# Reefing-PSU.net
KiCad netlist of a schematic drawn in Altium Designer
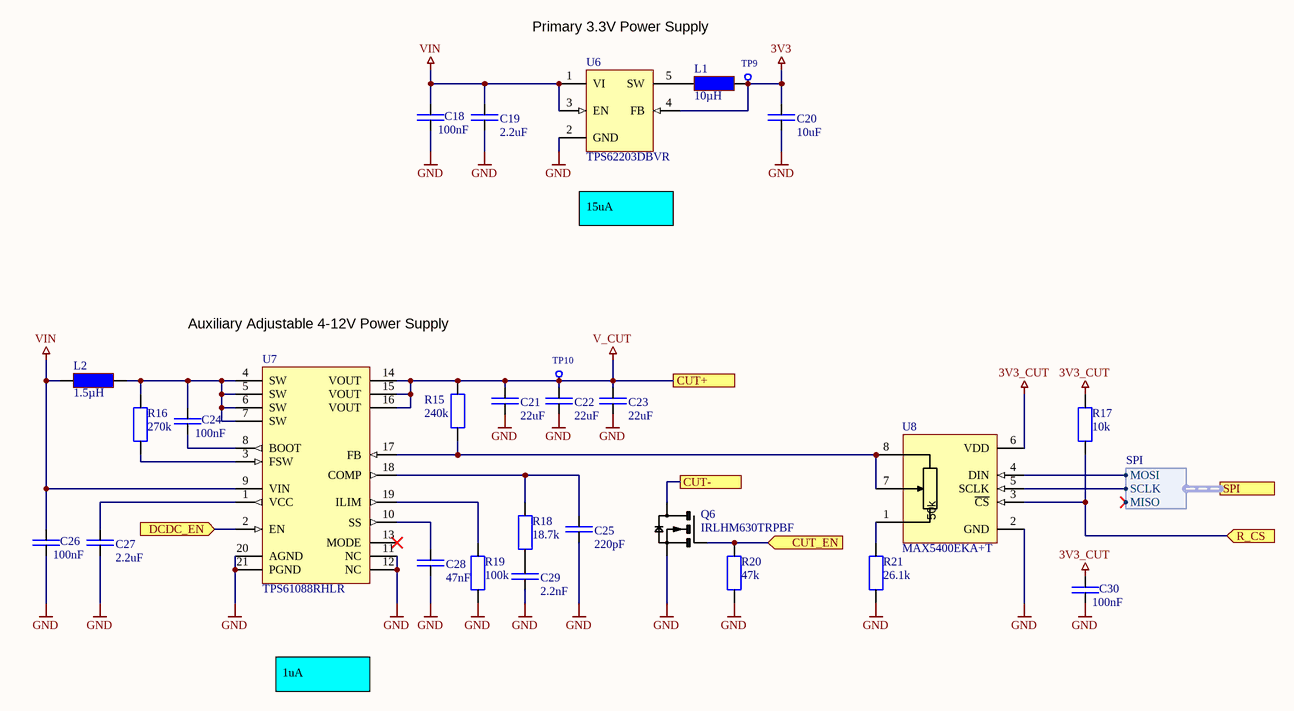
[diagram p0: Reefing-PSU.SchDoc]

(export (version "E")
  (design (tool "Eeschema 10.0.6"))
  (components
    (comp (ref "C18")
      (value "100nF")
      (footprint "SMD Keramikkondensator 0805")
      (description "SMD Ceramic Capacitor E6")
      (libsource (lib "Ceramic Capacitors-E6") (part "E6 - 100nF"))
    )
    (comp (ref "C19")
      (value "2.2uF")
      (footprint "SMD Keramikkondensator 0805")
      (description "SMD Ceramic Capacitor E6")
      (libsource (lib "Ceramic Capacitors-E6") (part "E6 - 2.2uF"))
    )
    (comp (ref "C20")
      (value "10uF")
      (footprint "SMD Keramikkondensator 0805")
      (description "SMD Ceramic Capacitor E6")
      (libsource (lib "Ceramic Capacitors-E6") (part "E6 - 10uF"))
    )
    (comp (ref "C21")
      (value "22uF")
      (footprint "SMD Keramikkondensator 0805")
      (description "SMD Ceramic Capacitor E6")
      (libsource (lib "Ceramic Capacitors-E6") (part "E6 - 22uF"))
    )
    (comp (ref "C22")
      (value "22uF")
      (footprint "SMD Keramikkondensator 0805")
      (description "SMD Ceramic Capacitor E6")
      (libsource (lib "Ceramic Capacitors-E6") (part "E6 - 22uF"))
    )
    (comp (ref "C23")
      (value "22uF")
      (footprint "SMD Keramikkondensator 0805")
      (description "SMD Ceramic Capacitor E6")
      (libsource (lib "Ceramic Capacitors-E6") (part "E6 - 22uF"))
    )
    (comp (ref "C24")
      (value "100nF")
      (footprint "SMD Keramikkondensator 0805")
      (description "SMD Ceramic Capacitor E6")
      (libsource (lib "Ceramic Capacitors-E6") (part "E6 - 100nF"))
    )
    (comp (ref "C25")
      (value "220pF")
      (footprint "SMD Keramikkondensator 0805")
      (description "SMD Ceramic Capacitor E6")
      (libsource (lib "Ceramic Capacitors-E6") (part "E6 - 220pF"))
    )
    (comp (ref "C26")
      (value "100nF")
      (footprint "SMD Keramikkondensator 0805")
      (description "SMD Ceramic Capacitor E6")
      (libsource (lib "Ceramic Capacitors-E6") (part "E6 - 100nF"))
    )
    (comp (ref "C27")
      (value "2.2uF")
      (footprint "SMD Keramikkondensator 0805")
      (description "SMD Ceramic Capacitor E6")
      (libsource (lib "Ceramic Capacitors-E6") (part "E6 - 2.2uF"))
    )
    (comp (ref "C28")
      (value "47nF")
      (footprint "SMD Keramikkondensator 0805")
      (description "SMD Ceramic Capacitor E6")
      (libsource (lib "Ceramic Capacitors-E6") (part "E6 - 47nF"))
    )
    (comp (ref "C29")
      (value "2.2nF")
      (footprint "SMD Keramikkondensator 0805")
      (description "SMD Ceramic Capacitor E6")
      (libsource (lib "Ceramic Capacitors-E6") (part "E6 - 2.2nF"))
    )
    (comp (ref "C30")
      (value "100nF")
      (footprint "SMD Keramikkondensator 0805")
      (description "SMD Ceramic Capacitor E6")
      (libsource (lib "Ceramic Capacitors-E6") (part "E6 - 100nF"))
    )
    (comp (ref "L1")
      (value "10µH")
      (footprint "SMD Inductor 4x4x1.8")
      (description "165mOhm SMD, 1.6A")
      (libsource (lib "Inductors") (part "Inductor 10µH / 1.6A"))
    )
    (comp (ref "L2")
      (value "1.5µH")
      (footprint "SMD Inductor 7.1x6.6")
      (description "8.5mΩ SMD, 7.1x6.6x5mm")
      (libsource (lib "Inductors") (part "Inductor 1.5µH / 10A"))
    )
    (comp (ref "Q6")
      (value "IRLHM630TRPBF")
      (footprint "SMD MOSFET DFN 3x3 EP")
      (description "N-Channel 30V 21A 3.5mOhm@4.5V")
      (libsource (lib "Electronic Switches") (part "IRLHM630TRPBF"))
    )
    (comp (ref "R15")
      (value "240k")
      (footprint "SMD Widerstand 0805")
      (description "SMD Chip Resistor E24")
      (libsource (lib "Resistors-E24") (part "E24 - 240k"))
    )
    (comp (ref "R16")
      (value "270k")
      (footprint "SMD Widerstand 0805")
      (description "SMD Chip Resistor E24")
      (libsource (lib "Resistors-E24") (part "E24 - 270k"))
    )
    (comp (ref "R17")
      (value "10k")
      (footprint "SMD Widerstand 0805")
      (description "SMD Chip Resistor E24")
      (libsource (lib "Resistors-E24") (part "E24 - 10k"))
    )
    (comp (ref "R18")
      (value "18.7k")
      (footprint "SMD Widerstand 0805")
      (description "SMD Chip Resistor E96")
      (libsource (lib "Resistors-E96") (part "E96 - 18.7k"))
    )
    (comp (ref "R19")
      (value "100k")
      (footprint "SMD Widerstand 0805")
      (description "SMD Chip Resistor E24")
      (libsource (lib "Resistors-E24") (part "E24 - 100k"))
    )
    (comp (ref "R20")
      (value "47k")
      (footprint "SMD Widerstand 0805")
      (description "SMD Chip Resistor E24")
      (libsource (lib "Resistors-E24") (part "E24 - 47k"))
    )
    (comp (ref "R21")
      (value "26.1k")
      (footprint "SMD Widerstand 0805")
      (description "SMD Chip Resistor E96")
      (libsource (lib "Resistors-E96") (part "E96 - 26.1k"))
    )
    (comp (ref "TP9")
      (value "X-TP")
      (footprint "SMD Testpunkt Ø1mm")
      (description "Testpunkt")
      (libsource (lib "Fleet-Monitor") (part "X-TP"))
    )
    (comp (ref "TP10")
      (value "X-TP")
      (footprint "SMD Testpunkt Ø1mm")
      (description "Testpunkt")
      (libsource (lib "Fleet-Monitor") (part "X-TP"))
    )
    (comp (ref "U6")
      (value "TPS62203DBVR")
      (footprint "SMD IC SOT-23-5")
      (libsource (lib "Voltage-Converter") (part "TPS62203DBVR"))
    )
    (comp (ref "U7")
      (value "TPS61088RHLR")
      (footprint "SMD IC VQFN-20")
      (description "10-A Fully-Integrated Synchronous Boost Converter")
      (libsource (lib "Voltage-Converter") (part "TPS61088RHLR"))
    )
    (comp (ref "U8")
      (value "MAX5400EKA+T")
      (footprint "SMD IC SOT-23-8")
      (description "Low-Drift Digital Potentiometer")
      (libsource (lib "Analog") (part "MAX5400EKA+T"))
    )
  )
  (nets
    (net (code "2") (name "/CUT-") (class "Default")
      (node (ref "Q6") (pin "D") (pinfunction "D_D") (pintype "passive"))
    )
    (net (code "3") (name "/CUT_EN") (class "Default")
      (node (ref "Q6") (pin "G") (pinfunction "G_G") (pintype "passive"))
      (node (ref "R20") (pin "2") (pinfunction "2_2") (pintype "passive"))
    )
    (net (code "4") (name "/DCDC_EN") (class "Default")
      (node (ref "U7") (pin "2") (pinfunction "EN_2") (pintype "input"))
    )
    (net (code "5") (name "/MOSI") (class "Default")
      (node (ref "U8") (pin "4") (pinfunction "DIN_4") (pintype "input"))
    )
    (net (code "6") (name "/R_CS") (class "Default")
      (node (ref "R17") (pin "1") (pinfunction "1_1") (pintype "passive"))
      (node (ref "U8") (pin "3") (pinfunction "~{CS}_3") (pintype "input"))
    )
    (net (code "7") (name "/SCLK") (class "Default")
      (node (ref "U8") (pin "5") (pinfunction "SCLK_5") (pintype "input"))
    )
    (net (code "9") (name "3V3") (class "Default")
      (node (ref "C20") (pin "2") (pinfunction "2_2") (pintype "passive"))
      (node (ref "L1") (pin "2") (pinfunction "2_2") (pintype "passive"))
      (node (ref "TP9") (pin "1") (pinfunction "1_1") (pintype "passive"))
      (node (ref "U6") (pin "4") (pinfunction "FB_4") (pintype "input"))
    )
    (net (code "10") (name "3V3_CUT") (class "Default")
      (node (ref "C30") (pin "2") (pinfunction "2_2") (pintype "passive"))
      (node (ref "R17") (pin "2") (pinfunction "2_2") (pintype "passive"))
      (node (ref "U8") (pin "6") (pinfunction "VDD_6") (pintype "passive"))
    )
    (net (code "11") (name "GND") (class "Default")
      (node (ref "C18") (pin "1") (pinfunction "1_1") (pintype "passive"))
      (node (ref "C19") (pin "1") (pinfunction "1_1") (pintype "passive"))
      (node (ref "C20") (pin "1") (pinfunction "1_1") (pintype "passive"))
      (node (ref "C21") (pin "1") (pinfunction "1_1") (pintype "passive"))
      (node (ref "C22") (pin "1") (pinfunction "1_1") (pintype "passive"))
      (node (ref "C23") (pin "1") (pinfunction "1_1") (pintype "passive"))
      (node (ref "C25") (pin "1") (pinfunction "1_1") (pintype "passive"))
      (node (ref "C26") (pin "1") (pinfunction "1_1") (pintype "passive"))
      (node (ref "C27") (pin "1") (pinfunction "1_1") (pintype "passive"))
      (node (ref "C28") (pin "1") (pinfunction "1_1") (pintype "passive"))
      (node (ref "C29") (pin "1") (pinfunction "1_1") (pintype "passive"))
      (node (ref "C30") (pin "1") (pinfunction "1_1") (pintype "passive"))
      (node (ref "Q6") (pin "S") (pinfunction "S_S") (pintype "passive"))
      (node (ref "R19") (pin "1") (pinfunction "1_1") (pintype "passive"))
      (node (ref "R20") (pin "1") (pinfunction "1_1") (pintype "passive"))
      (node (ref "R21") (pin "1") (pinfunction "1_1") (pintype "passive"))
      (node (ref "U6") (pin "2") (pinfunction "GND_2") (pintype "passive"))
      (node (ref "U7") (pin "11") (pinfunction "NC_11") (pintype "passive"))
      (node (ref "U7") (pin "12") (pinfunction "NC_12") (pintype "passive"))
      (node (ref "U7") (pin "20") (pinfunction "AGND_20") (pintype "passive"))
      (node (ref "U7") (pin "21") (pinfunction "PGND_21") (pintype "passive"))
      (node (ref "U8") (pin "2") (pinfunction "GND_2") (pintype "passive"))
    )
    (net (code "12") (name "Net-(C24-Pad2)") (class "Default")
      (node (ref "C24") (pin "2") (pinfunction "2_2") (pintype "passive"))
      (node (ref "L2") (pin "2") (pinfunction "2_2") (pintype "passive"))
      (node (ref "R16") (pin "2") (pinfunction "2_2") (pintype "passive"))
      (node (ref "U7") (pin "4") (pinfunction "SW_4") (pintype "passive"))
      (node (ref "U7") (pin "5") (pinfunction "SW_5") (pintype "passive"))
      (node (ref "U7") (pin "6") (pinfunction "SW_6") (pintype "passive"))
      (node (ref "U7") (pin "7") (pinfunction "SW_7") (pintype "passive"))
    )
    (net (code "13") (name "Net-(C29-Pad2)") (class "Default")
      (node (ref "C29") (pin "2") (pinfunction "2_2") (pintype "passive"))
      (node (ref "R18") (pin "1") (pinfunction "1_1") (pintype "passive"))
    )
    (net (code "14") (name "Net-(U6-SW)") (class "Default")
      (node (ref "L1") (pin "1") (pinfunction "1_1") (pintype "passive"))
      (node (ref "U6") (pin "5") (pinfunction "SW_5") (pintype "passive"))
    )
    (net (code "15") (name "Net-(U7-BOOT)") (class "Default")
      (node (ref "C24") (pin "1") (pinfunction "1_1") (pintype "passive"))
      (node (ref "U7") (pin "8") (pinfunction "BOOT_8") (pintype "output"))
    )
    (net (code "16") (name "Net-(U7-COMP)") (class "Default")
      (node (ref "C25") (pin "2") (pinfunction "2_2") (pintype "passive"))
      (node (ref "R18") (pin "2") (pinfunction "2_2") (pintype "passive"))
      (node (ref "U7") (pin "18") (pinfunction "COMP_18") (pintype "output"))
    )
    (net (code "17") (name "Net-(U7-FB)") (class "Default")
      (node (ref "R15") (pin "1") (pinfunction "1_1") (pintype "passive"))
      (node (ref "U7") (pin "17") (pinfunction "FB_17") (pintype "input"))
      (node (ref "U8") (pin "7") (pinfunction "W_7") (pintype "passive"))
      (node (ref "U8") (pin "8") (pinfunction "H_8") (pintype "passive"))
    )
    (net (code "18") (name "Net-(U7-FSW)") (class "Default")
      (node (ref "R16") (pin "1") (pinfunction "1_1") (pintype "passive"))
      (node (ref "U7") (pin "3") (pinfunction "FSW_3") (pintype "input"))
    )
    (net (code "19") (name "Net-(U7-ILIM)") (class "Default")
      (node (ref "R19") (pin "2") (pinfunction "2_2") (pintype "passive"))
      (node (ref "U7") (pin "19") (pinfunction "ILIM_19") (pintype "output"))
    )
    (net (code "20") (name "Net-(U7-SS)") (class "Default")
      (node (ref "C28") (pin "2") (pinfunction "2_2") (pintype "passive"))
      (node (ref "U7") (pin "10") (pinfunction "SS_10") (pintype "output"))
    )
    (net (code "21") (name "Net-(U7-VCC)") (class "Default")
      (node (ref "C27") (pin "2") (pinfunction "2_2") (pintype "passive"))
      (node (ref "U7") (pin "1") (pinfunction "VCC_1") (pintype "output"))
    )
    (net (code "22") (name "Net-(U8-L)") (class "Default")
      (node (ref "R21") (pin "2") (pinfunction "2_2") (pintype "passive"))
      (node (ref "U8") (pin "1") (pinfunction "L_1") (pintype "passive"))
    )
    (net (code "23") (name "VIN") (class "Default")
      (node (ref "C18") (pin "2") (pinfunction "2_2") (pintype "passive"))
      (node (ref "C19") (pin "2") (pinfunction "2_2") (pintype "passive"))
      (node (ref "C26") (pin "2") (pinfunction "2_2") (pintype "passive"))
      (node (ref "L2") (pin "1") (pinfunction "1_1") (pintype "passive"))
      (node (ref "U6") (pin "1") (pinfunction "VI_1") (pintype "passive"))
      (node (ref "U6") (pin "3") (pinfunction "EN_3") (pintype "input"))
      (node (ref "U7") (pin "9") (pinfunction "VIN_9") (pintype "passive"))
    )
    (net (code "24") (name "V_CUT") (class "Default")
      (node (ref "C21") (pin "2") (pinfunction "2_2") (pintype "passive"))
      (node (ref "C22") (pin "2") (pinfunction "2_2") (pintype "passive"))
      (node (ref "C23") (pin "2") (pinfunction "2_2") (pintype "passive"))
      (node (ref "R15") (pin "2") (pinfunction "2_2") (pintype "passive"))
      (node (ref "TP10") (pin "1") (pinfunction "1_1") (pintype "passive"))
      (node (ref "U7") (pin "14") (pinfunction "VOUT_14") (pintype "passive"))
      (node (ref "U7") (pin "15") (pinfunction "VOUT_15") (pintype "passive"))
      (node (ref "U7") (pin "16") (pinfunction "VOUT_16") (pintype "passive"))
    )
    (net (code "25") (name "unconnected-(U7-MODE-Pad13)") (class "Default")
      (node (ref "U7") (pin "13") (pinfunction "MODE_13") (pintype "passive+no_connect"))
    )
  )
)
